# WalkieTalkie_Basic.net
KiCad netlist of a schematic drawn in EAGLE
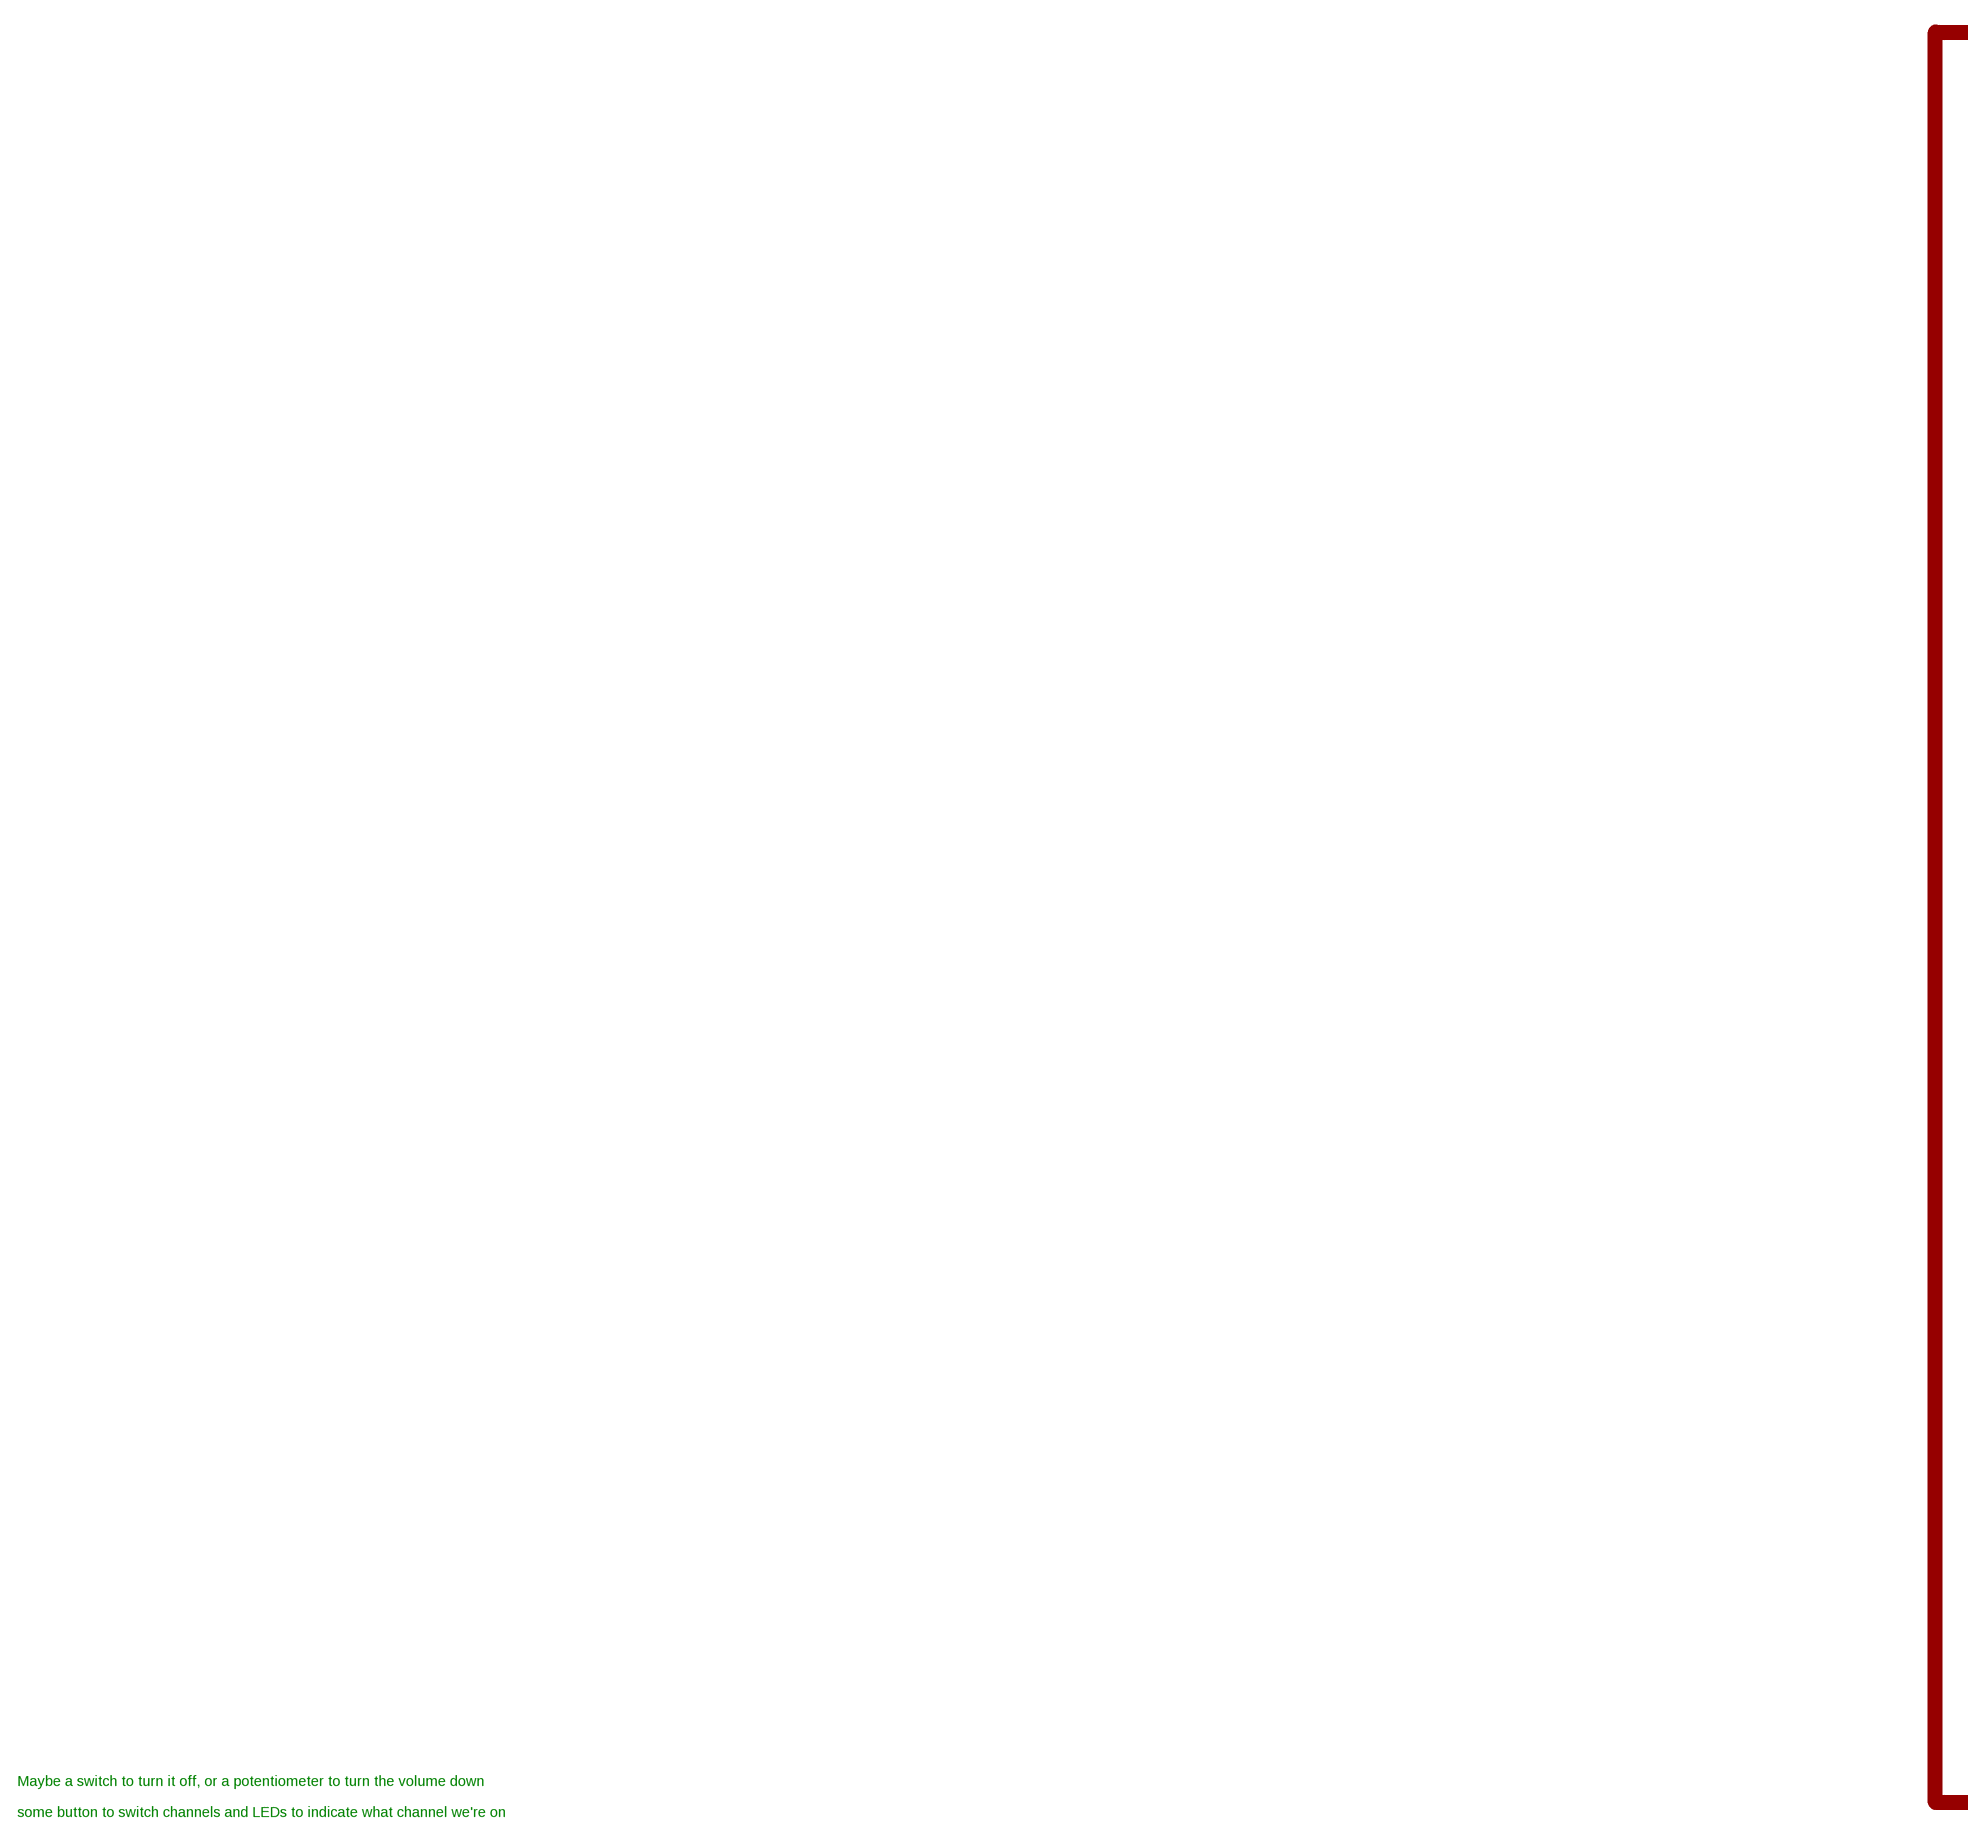
[diagram p0: schematic, sheet 1, part 1 of 2]
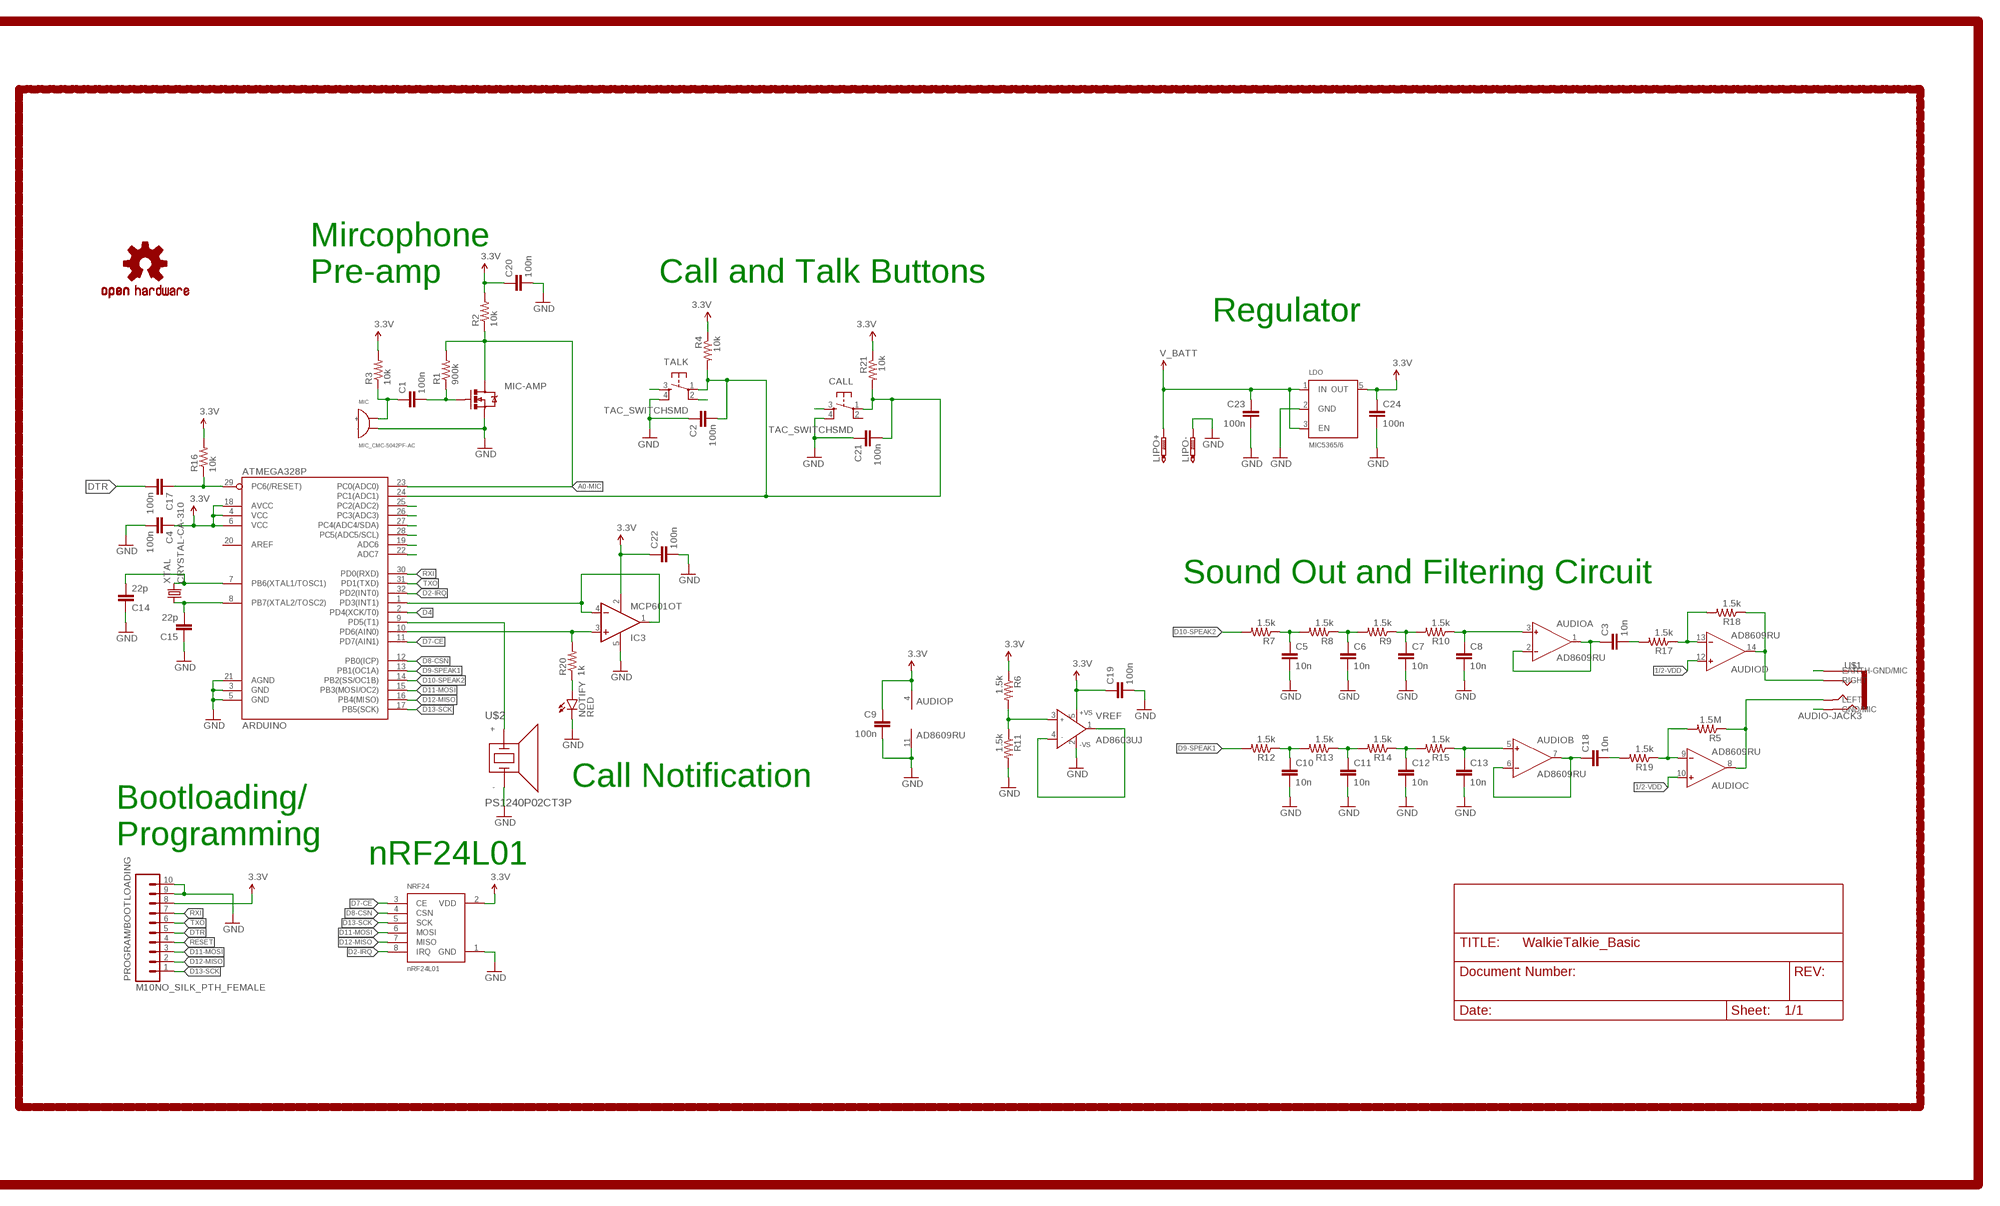
[diagram p1: schematic, sheet 1, part 2 of 2]

(export (version "E")
  (design (tool "Eeschema 10.0.6"))
  (components
    (comp (ref "ARDUINO")
      (value "ATMEGA328P")
      (footprint "eagle-import:TQFP32-08")
      (libsource (lib "eagle-import") (part "ATMEGA328_SMT-OHMOD"))
    )
    (comp (ref "AUDIO")
      (value "AD8609RU")
      (footprint "eagle-import:TSSOP14")
      (fields (field (name "MF") "ALTERA CORPORATION") (field (name "MPN") "AD8609ARUZ"))
      (libsource (lib "eagle-import") (part "AD8609RU"))
    )
    (comp (ref "C1")
      (value "100n")
      (footprint "eagle-import:C0402")
      (libsource (lib "eagle-import") (part "C-EUC0402"))
    )
    (comp (ref "C2")
      (value "100n")
      (footprint "eagle-import:C0402")
      (libsource (lib "eagle-import") (part "C-EUC0402"))
    )
    (comp (ref "C3")
      (value "10n")
      (footprint "eagle-import:C0402")
      (libsource (lib "eagle-import") (part "C-EUC0402"))
    )
    (comp (ref "C4")
      (value "100n")
      (footprint "eagle-import:C0402")
      (libsource (lib "eagle-import") (part "C-EUC0402"))
    )
    (comp (ref "C5")
      (value "10n")
      (footprint "eagle-import:C0402")
      (libsource (lib "eagle-import") (part "C-EUC0402"))
    )
    (comp (ref "C6")
      (value "10n")
      (footprint "eagle-import:C0402")
      (libsource (lib "eagle-import") (part "C-EUC0402"))
    )
    (comp (ref "C7")
      (value "10n")
      (footprint "eagle-import:C0402")
      (libsource (lib "eagle-import") (part "C-EUC0402"))
    )
    (comp (ref "C8")
      (value "10n")
      (footprint "eagle-import:C0402")
      (libsource (lib "eagle-import") (part "C-EUC0402"))
    )
    (comp (ref "C9")
      (value "100n")
      (footprint "eagle-import:C0402")
      (libsource (lib "eagle-import") (part "C-EUC0402"))
    )
    (comp (ref "C10")
      (value "10n")
      (footprint "eagle-import:C0402")
      (libsource (lib "eagle-import") (part "C-EUC0402"))
    )
    (comp (ref "C11")
      (value "10n")
      (footprint "eagle-import:C0402")
      (libsource (lib "eagle-import") (part "C-EUC0402"))
    )
    (comp (ref "C12")
      (value "10n")
      (footprint "eagle-import:C0402")
      (libsource (lib "eagle-import") (part "C-EUC0402"))
    )
    (comp (ref "C13")
      (value "10n")
      (footprint "eagle-import:C0402")
      (libsource (lib "eagle-import") (part "C-EUC0402"))
    )
    (comp (ref "C14")
      (value "22p")
      (footprint "eagle-import:C0402")
      (libsource (lib "eagle-import") (part "C-EUC0402"))
    )
    (comp (ref "C15")
      (value "22p")
      (footprint "eagle-import:C0402")
      (libsource (lib "eagle-import") (part "C-EUC0402"))
    )
    (comp (ref "C17")
      (value "100n")
      (footprint "eagle-import:C0402")
      (libsource (lib "eagle-import") (part "C-EUC0402"))
    )
    (comp (ref "C18")
      (value "10n")
      (footprint "eagle-import:C0402")
      (libsource (lib "eagle-import") (part "C-EUC0402"))
    )
    (comp (ref "C19")
      (value "100n")
      (footprint "eagle-import:C0402")
      (libsource (lib "eagle-import") (part "C-EUC0402"))
    )
    (comp (ref "C20")
      (value "100n")
      (footprint "eagle-import:C0402")
      (libsource (lib "eagle-import") (part "C-EUC0402"))
    )
    (comp (ref "C21")
      (value "100n")
      (footprint "eagle-import:C0402")
      (libsource (lib "eagle-import") (part "C-EUC0402"))
    )
    (comp (ref "C22")
      (value "100n")
      (footprint "eagle-import:C0402")
      (libsource (lib "eagle-import") (part "C-EUC0402"))
    )
    (comp (ref "C23")
      (value "100n")
      (footprint "eagle-import:C0402")
      (libsource (lib "eagle-import") (part "C-EUC0402"))
    )
    (comp (ref "C24")
      (value "100n")
      (footprint "eagle-import:C0402")
      (libsource (lib "eagle-import") (part "C-EUC0402"))
    )
    (comp (ref "CALL")
      (value "TAC_SWITCHSMD")
      (footprint "eagle-import:TACTILE-SWITCH-SMD")
      (libsource (lib "eagle-import") (part "TAC_SWITCHSMD"))
    )
    (comp (ref "IC3")
      (value "MCP601OT")
      (footprint "eagle-import:SOT23-5")
      (libsource (lib "eagle-import") (part "MCP601OT"))
    )
    (comp (ref "LDO")
      (value "MIC5365/6")
      (footprint "eagle-import:SC-70-5")
      (libsource (lib "eagle-import") (part "MIC5365/6"))
    )
    (comp (ref "LIPO")
      (value "BATT-CONNECT")
      (footprint "eagle-import:HOLE")
      (libsource (lib "eagle-import") (part "BATT-CONNECT"))
    )
    (comp (ref "LOGO1")
      (value "OSHW-LOGOS")
      (footprint "eagle-import:OSHW-LOGO-S")
      (libsource (lib "eagle-import") (part "OSHW-LOGOS"))
    )
    (comp (ref "MIC")
      (value "MIC_CMC-5042PF-AC")
      (footprint "eagle-import:MIC_01")
      (libsource (lib "eagle-import") (part "MIC_CMC-5042PF-AC"))
    )
    (comp (ref "MIC-AMP")
      (value "MOSFET-NCHANNELBSS123LT1G")
      (footprint "eagle-import:SOT23-3")
      (libsource (lib "eagle-import") (part "MOSFET-NCHANNELBSS123LT1G"))
    )
    (comp (ref "NOTIFY")
      (value "RED")
      (footprint "eagle-import:LED-0603")
      (libsource (lib "eagle-import") (part "LED-RED0603"))
    )
    (comp (ref "NRF24")
      (value "NRF24L01-BREAKOUT")
      (footprint "eagle-import:NRF24L01-BREAKOUT")
      (libsource (lib "eagle-import") (part "NRF24L01-BREAKOUT"))
    )
    (comp (ref "PROGRAM/BOOTLOADING")
      (value "M10NO_SILK_PTH_FEMALE")
      (footprint "eagle-import:1X10_NO_SILK")
      (libsource (lib "eagle-import") (part "M10NO_SILK_PTH_FEMALE"))
    )
    (comp (ref "R1")
      (value "900k")
      (footprint "eagle-import:R0402")
      (libsource (lib "eagle-import") (part "R-US_R0402"))
    )
    (comp (ref "R2")
      (value "10k")
      (footprint "eagle-import:R0402")
      (libsource (lib "eagle-import") (part "R-US_R0402"))
    )
    (comp (ref "R3")
      (value "10k")
      (footprint "eagle-import:R0402")
      (libsource (lib "eagle-import") (part "R-US_R0402"))
    )
    (comp (ref "R4")
      (value "10k")
      (footprint "eagle-import:R0402")
      (libsource (lib "eagle-import") (part "R-US_R0402"))
    )
    (comp (ref "R5")
      (value "1.5M")
      (footprint "eagle-import:R0402")
      (libsource (lib "eagle-import") (part "R-US_R0402"))
    )
    (comp (ref "R6")
      (value "1.5k")
      (footprint "eagle-import:R0402")
      (libsource (lib "eagle-import") (part "R-US_R0402"))
    )
    (comp (ref "R7")
      (value "1.5k")
      (footprint "eagle-import:R0402")
      (libsource (lib "eagle-import") (part "R-US_R0402"))
    )
    (comp (ref "R8")
      (value "1.5k")
      (footprint "eagle-import:R0402")
      (libsource (lib "eagle-import") (part "R-US_R0402"))
    )
    (comp (ref "R9")
      (value "1.5k")
      (footprint "eagle-import:R0402")
      (libsource (lib "eagle-import") (part "R-US_R0402"))
    )
    (comp (ref "R10")
      (value "1.5k")
      (footprint "eagle-import:R0402")
      (libsource (lib "eagle-import") (part "R-US_R0402"))
    )
    (comp (ref "R11")
      (value "1.5k")
      (footprint "eagle-import:R0402")
      (libsource (lib "eagle-import") (part "R-US_R0402"))
    )
    (comp (ref "R12")
      (value "1.5k")
      (footprint "eagle-import:R0402")
      (libsource (lib "eagle-import") (part "R-US_R0402"))
    )
    (comp (ref "R13")
      (value "1.5k")
      (footprint "eagle-import:R0402")
      (libsource (lib "eagle-import") (part "R-US_R0402"))
    )
    (comp (ref "R14")
      (value "1.5k")
      (footprint "eagle-import:R0402")
      (libsource (lib "eagle-import") (part "R-US_R0402"))
    )
    (comp (ref "R15")
      (value "1.5k")
      (footprint "eagle-import:R0402")
      (libsource (lib "eagle-import") (part "R-US_R0402"))
    )
    (comp (ref "R16")
      (value "10k")
      (footprint "eagle-import:R0402")
      (libsource (lib "eagle-import") (part "R-US_R0402"))
    )
    (comp (ref "R17")
      (value "1.5k")
      (footprint "eagle-import:R0402")
      (libsource (lib "eagle-import") (part "R-US_R0402"))
    )
    (comp (ref "R18")
      (value "1.5k")
      (footprint "eagle-import:R0402")
      (libsource (lib "eagle-import") (part "R-US_R0402"))
    )
    (comp (ref "R19")
      (value "1.5k")
      (footprint "eagle-import:R0402")
      (libsource (lib "eagle-import") (part "R-US_R0402"))
    )
    (comp (ref "R20")
      (value "1k")
      (footprint "eagle-import:R0402")
      (libsource (lib "eagle-import") (part "R-US_R0402"))
    )
    (comp (ref "R21")
      (value "10k")
      (footprint "eagle-import:R0402")
      (libsource (lib "eagle-import") (part "R-US_R0402"))
    )
    (comp (ref "TALK")
      (value "TAC_SWITCHSMD")
      (footprint "eagle-import:TACTILE-SWITCH-SMD")
      (libsource (lib "eagle-import") (part "TAC_SWITCHSMD"))
    )
    (comp (ref "U$1")
      (value "AUDIO-JACK3")
      (footprint "eagle-import:AUDIO-JACK-TRRS-SMD")
      (libsource (lib "eagle-import") (part "AUDIO-JACK3"))
    )
    (comp (ref "U$2")
      (value "PS1240P02CT3P")
      (footprint "eagle-import:PIEZO-1")
      (libsource (lib "eagle-import") (part "PS1240P02CT3P"))
    )
    (comp (ref "VREF")
      (value "AD8603UJ")
      (footprint "eagle-import:SOT23-5")
      (fields (field (name "MF") "ALTERA CORPORATION") (field (name "MPN") "AD8603AUJZ-REEL7"))
      (libsource (lib "eagle-import") (part "AD8603UJ"))
    )
    (comp (ref "XTAL")
      (value "CRYSTAL-CA-310")
      (footprint "eagle-import:CA-301")
      (libsource (lib "eagle-import") (part "CRYSTAL-CA-310"))
    )
  )
  (nets
    (net (code "1") (name "1{slash}2-VDD") (class "Default")
      (node (ref "AUDIO") (pin "10") (pinfunction "IN+_10") (pintype "input"))
      (node (ref "AUDIO") (pin "12") (pinfunction "IN+_12") (pintype "input"))
      (node (ref "VREF") (pin "1") (pinfunction "OUT_1") (pintype "output"))
      (node (ref "VREF") (pin "4") (pinfunction "IN-_4") (pintype "input"))
    )
    (net (code "2") (name "3.3V") (class "Default")
      (node (ref "ARDUINO") (pin "18") (pinfunction "AVCC_18") (pintype "bidirectional"))
      (node (ref "ARDUINO") (pin "4") (pinfunction "VCC_4") (pintype "bidirectional"))
      (node (ref "ARDUINO") (pin "6") (pinfunction "VCC_6") (pintype "bidirectional"))
      (node (ref "AUDIO") (pin "4") (pinfunction "V+_4") (pintype "power_in"))
      (node (ref "C19") (pin "1") (pinfunction "1_1") (pintype "passive"))
      (node (ref "C20") (pin "1") (pinfunction "1_1") (pintype "passive"))
      (node (ref "C22") (pin "1") (pinfunction "1_1") (pintype "passive"))
      (node (ref "C24") (pin "1") (pinfunction "1_1") (pintype "passive"))
      (node (ref "C4") (pin "1") (pinfunction "1_1") (pintype "passive"))
      (node (ref "C9") (pin "1") (pinfunction "1_1") (pintype "passive"))
      (node (ref "IC3") (pin "2") (pinfunction "V-_2") (pintype "power_in"))
      (node (ref "LDO") (pin "5") (pinfunction "OUT_5") (pintype "bidirectional"))
      (node (ref "NRF24") (pin "2") (pinfunction "VDD_2") (pintype "bidirectional"))
      (node (ref "PROGRAM/BOOTLOADING") (pin "8") (pinfunction "8_8") (pintype "passive"))
      (node (ref "R16") (pin "2") (pinfunction "2_2") (pintype "passive"))
      (node (ref "R2") (pin "2") (pinfunction "2_2") (pintype "passive"))
      (node (ref "R21") (pin "1") (pinfunction "1_1") (pintype "passive"))
      (node (ref "R3") (pin "2") (pinfunction "2_2") (pintype "passive"))
      (node (ref "R4") (pin "1") (pinfunction "1_1") (pintype "passive"))
      (node (ref "R6") (pin "1") (pinfunction "1_1") (pintype "passive"))
      (node (ref "VREF") (pin "5") (pinfunction "+VS_5") (pintype "input"))
    )
    (net (code "3") (name "A0-MIC") (class "Default")
      (node (ref "ARDUINO") (pin "23") (pinfunction "PC0(ADC0)_23") (pintype "bidirectional"))
      (node (ref "MIC-AMP") (pin "3") (pinfunction "D_3") (pintype "passive"))
      (node (ref "R1") (pin "2") (pinfunction "2_2") (pintype "passive"))
      (node (ref "R2") (pin "1") (pinfunction "1_1") (pintype "passive"))
    )
    (net (code "4") (name "D2-IRQ") (class "Default")
      (node (ref "ARDUINO") (pin "32") (pinfunction "PD2(INT0)_32") (pintype "bidirectional"))
      (node (ref "NRF24") (pin "8") (pinfunction "IRQ_8") (pintype "bidirectional"))
    )
    (net (code "5") (name "D4") (class "Default")
      (node (ref "ARDUINO") (pin "2") (pinfunction "PD4(XCK/T0)_2") (pintype "bidirectional"))
    )
    (net (code "6") (name "D7-CE") (class "Default")
      (node (ref "ARDUINO") (pin "11") (pinfunction "PD7(AIN1)_11") (pintype "bidirectional"))
      (node (ref "NRF24") (pin "3") (pinfunction "CE_3") (pintype "bidirectional"))
    )
    (net (code "7") (name "D8-CSN") (class "Default")
      (node (ref "ARDUINO") (pin "12") (pinfunction "PB0(ICP)_12") (pintype "bidirectional"))
      (node (ref "NRF24") (pin "4") (pinfunction "CSN_4") (pintype "bidirectional"))
    )
    (net (code "8") (name "D9-SPEAK1") (class "Default")
      (node (ref "ARDUINO") (pin "13") (pinfunction "PB1(OC1A)_13") (pintype "bidirectional"))
      (node (ref "R12") (pin "2") (pinfunction "2_2") (pintype "passive"))
    )
    (net (code "9") (name "D10-SPEAK2") (class "Default")
      (node (ref "ARDUINO") (pin "14") (pinfunction "PB2(SS/OC1B)_14") (pintype "bidirectional"))
      (node (ref "R7") (pin "2") (pinfunction "2_2") (pintype "passive"))
    )
    (net (code "10") (name "D11-MOSI") (class "Default")
      (node (ref "ARDUINO") (pin "15") (pinfunction "PB3(MOSI/OC2)_15") (pintype "bidirectional"))
      (node (ref "NRF24") (pin "6") (pinfunction "MOSI_6") (pintype "bidirectional"))
      (node (ref "PROGRAM/BOOTLOADING") (pin "3") (pinfunction "3_3") (pintype "passive"))
    )
    (net (code "11") (name "D12-MISO") (class "Default")
      (node (ref "ARDUINO") (pin "16") (pinfunction "PB4(MISO)_16") (pintype "bidirectional"))
      (node (ref "NRF24") (pin "7") (pinfunction "MISO_7") (pintype "bidirectional"))
      (node (ref "PROGRAM/BOOTLOADING") (pin "2") (pinfunction "2_2") (pintype "passive"))
    )
    (net (code "12") (name "D13-SCK") (class "Default")
      (node (ref "ARDUINO") (pin "17") (pinfunction "PB5(SCK)_17") (pintype "bidirectional"))
      (node (ref "NRF24") (pin "5") (pinfunction "SCK_5") (pintype "bidirectional"))
      (node (ref "PROGRAM/BOOTLOADING") (pin "1") (pinfunction "1_1") (pintype "passive"))
    )
    (net (code "13") (name "DTR") (class "Default")
      (node (ref "C17") (pin "2") (pinfunction "2_2") (pintype "passive"))
      (node (ref "PROGRAM/BOOTLOADING") (pin "5") (pinfunction "5_5") (pintype "passive"))
    )
    (net (code "14") (name "GND") (class "Default")
      (node (ref "ARDUINO") (pin "21") (pinfunction "AGND_21") (pintype "bidirectional"))
      (node (ref "ARDUINO") (pin "3") (pinfunction "GND_3") (pintype "bidirectional"))
      (node (ref "ARDUINO") (pin "5") (pinfunction "GND_5") (pintype "bidirectional"))
      (node (ref "AUDIO") (pin "11") (pinfunction "V-_11") (pintype "power_in"))
      (node (ref "C10") (pin "2") (pinfunction "2_2") (pintype "passive"))
      (node (ref "C11") (pin "2") (pinfunction "2_2") (pintype "passive"))
      (node (ref "C12") (pin "2") (pinfunction "2_2") (pintype "passive"))
      (node (ref "C13") (pin "2") (pinfunction "2_2") (pintype "passive"))
      (node (ref "C14") (pin "1") (pinfunction "1_1") (pintype "passive"))
      (node (ref "C15") (pin "1") (pinfunction "1_1") (pintype "passive"))
      (node (ref "C19") (pin "2") (pinfunction "2_2") (pintype "passive"))
      (node (ref "C2") (pin "1") (pinfunction "1_1") (pintype "passive"))
      (node (ref "C20") (pin "2") (pinfunction "2_2") (pintype "passive"))
      (node (ref "C21") (pin "1") (pinfunction "1_1") (pintype "passive"))
      (node (ref "C22") (pin "2") (pinfunction "2_2") (pintype "passive"))
      (node (ref "C23") (pin "2") (pinfunction "2_2") (pintype "passive"))
      (node (ref "C24") (pin "2") (pinfunction "2_2") (pintype "passive"))
      (node (ref "C4") (pin "2") (pinfunction "2_2") (pintype "passive"))
      (node (ref "C5") (pin "2") (pinfunction "2_2") (pintype "passive"))
      (node (ref "C6") (pin "2") (pinfunction "2_2") (pintype "passive"))
      (node (ref "C7") (pin "2") (pinfunction "2_2") (pintype "passive"))
      (node (ref "C8") (pin "2") (pinfunction "2_2") (pintype "passive"))
      (node (ref "C9") (pin "2") (pinfunction "2_2") (pintype "passive"))
      (node (ref "CALL") (pin "4") (pinfunction "4_4") (pintype "passive"))
      (node (ref "IC3") (pin "5") (pinfunction "V+_5") (pintype "power_in"))
      (node (ref "LDO") (pin "2") (pinfunction "GND_2") (pintype "bidirectional"))
      (node (ref "LIPO") (pin "P$2") (pinfunction "TP_P$2") (pintype "input"))
      (node (ref "MIC") (pin "-") (pinfunction "-_-") (pintype "bidirectional"))
      (node (ref "MIC-AMP") (pin "2") (pinfunction "S_2") (pintype "passive"))
      (node (ref "NOTIFY") (pin "C") (pinfunction "C_C") (pintype "passive"))
      (node (ref "NRF24") (pin "1") (pinfunction "GND_1") (pintype "bidirectional"))
      (node (ref "PROGRAM/BOOTLOADING") (pin "10") (pinfunction "10_10") (pintype "passive"))
      (node (ref "PROGRAM/BOOTLOADING") (pin "9") (pinfunction "9_9") (pintype "passive"))
      (node (ref "R11") (pin "2") (pinfunction "2_2") (pintype "passive"))
      (node (ref "TALK") (pin "4") (pinfunction "4_4") (pintype "passive"))
      (node (ref "U$2") (pin "-") (pinfunction "-_-") (pintype "bidirectional"))
      (node (ref "VREF") (pin "2") (pinfunction "-VS_2") (pintype "input"))
    )
    (net (code "15") (name "Net-(ARDUINO-PB6(XTAL1{slash}TOSC1))") (class "Default")
      (node (ref "ARDUINO") (pin "7") (pinfunction "PB6(XTAL1/TOSC1)_7") (pintype "bidirectional"))
      (node (ref "C14") (pin "2") (pinfunction "2_2") (pintype "passive"))
      (node (ref "XTAL") (pin "2") (pinfunction "2_2") (pintype "passive"))
    )
    (net (code "16") (name "Net-(ARDUINO-PB7(XTAL2{slash}TOSC2))") (class "Default")
      (node (ref "ARDUINO") (pin "8") (pinfunction "PB7(XTAL2/TOSC2)_8") (pintype "bidirectional"))
      (node (ref "C15") (pin "2") (pinfunction "2_2") (pintype "passive"))
      (node (ref "XTAL") (pin "1") (pinfunction "1_1") (pintype "passive"))
    )
    (net (code "17") (name "Net-(ARDUINO-PC1(ADC1))") (class "Default")
      (node (ref "ARDUINO") (pin "24") (pinfunction "PC1(ADC1)_24") (pintype "bidirectional"))
      (node (ref "C2") (pin "2") (pinfunction "2_2") (pintype "passive"))
      (node (ref "C21") (pin "2") (pinfunction "2_2") (pintype "passive"))
      (node (ref "CALL") (pin "1") (pinfunction "1_1") (pintype "passive"))
      (node (ref "R21") (pin "2") (pinfunction "2_2") (pintype "passive"))
      (node (ref "R4") (pin "2") (pinfunction "2_2") (pintype "passive"))
      (node (ref "TALK") (pin "1") (pinfunction "1_1") (pintype "passive"))
    )
    (net (code "18") (name "Net-(ARDUINO-PD3(INT1))") (class "Default")
      (node (ref "ARDUINO") (pin "1") (pinfunction "PD3(INT1)_1") (pintype "bidirectional"))
      (node (ref "IC3") (pin "1") (pinfunction "OUT_1") (pintype "output"))
      (node (ref "IC3") (pin "4") (pinfunction "-IN_4") (pintype "input"))
    )
    (net (code "19") (name "Net-(ARDUINO-PD5(T1))") (class "Default")
      (node (ref "ARDUINO") (pin "9") (pinfunction "PD5(T1)_9") (pintype "bidirectional"))
      (node (ref "U$2") (pin "+") (pinfunction "+_+") (pintype "bidirectional"))
    )
    (net (code "20") (name "Net-(ARDUINO-PD6(AIN0))") (class "Default")
      (node (ref "ARDUINO") (pin "10") (pinfunction "PD6(AIN0)_10") (pintype "bidirectional"))
      (node (ref "IC3") (pin "3") (pinfunction "+IN_3") (pintype "input"))
      (node (ref "R20") (pin "2") (pinfunction "2_2") (pintype "passive"))
    )
    (net (code "21") (name "Net-(AUDIOA-IN+)") (class "Default")
      (node (ref "AUDIO") (pin "3") (pinfunction "IN+_3") (pintype "input"))
      (node (ref "C8") (pin "1") (pinfunction "1_1") (pintype "passive"))
      (node (ref "R10") (pin "1") (pinfunction "1_1") (pintype "passive"))
    )
    (net (code "22") (name "Net-(AUDIOA-IN-)") (class "Default")
      (node (ref "AUDIO") (pin "1") (pinfunction "OUT_1") (pintype "output"))
      (node (ref "AUDIO") (pin "2") (pinfunction "IN-_2") (pintype "input"))
      (node (ref "C3") (pin "1") (pinfunction "1_1") (pintype "passive"))
    )
    (net (code "23") (name "Net-(AUDIOB-IN+)") (class "Default")
      (node (ref "AUDIO") (pin "5") (pinfunction "IN+_5") (pintype "input"))
      (node (ref "C13") (pin "1") (pinfunction "1_1") (pintype "passive"))
      (node (ref "R15") (pin "1") (pinfunction "1_1") (pintype "passive"))
    )
    (net (code "24") (name "Net-(AUDIOB-IN-)") (class "Default")
      (node (ref "AUDIO") (pin "6") (pinfunction "IN-_6") (pintype "input"))
      (node (ref "AUDIO") (pin "7") (pinfunction "OUT_7") (pintype "output"))
      (node (ref "C18") (pin "1") (pinfunction "1_1") (pintype "passive"))
    )
    (net (code "25") (name "Net-(AUDIOC-IN-)") (class "Default")
      (node (ref "AUDIO") (pin "9") (pinfunction "IN-_9") (pintype "input"))
      (node (ref "R19") (pin "1") (pinfunction "1_1") (pintype "passive"))
      (node (ref "R5") (pin "2") (pinfunction "2_2") (pintype "passive"))
    )
    (net (code "26") (name "Net-(AUDIOC-OUT)") (class "Default")
      (node (ref "AUDIO") (pin "8") (pinfunction "OUT_8") (pintype "output"))
      (node (ref "R5") (pin "1") (pinfunction "1_1") (pintype "passive"))
      (node (ref "U$1") (pin "TIP") (pinfunction "LEFT_TIP") (pintype "bidirectional"))
    )
    (net (code "27") (name "Net-(AUDIOD-IN-)") (class "Default")
      (node (ref "AUDIO") (pin "13") (pinfunction "IN-_13") (pintype "input"))
      (node (ref "R17") (pin "1") (pinfunction "1_1") (pintype "passive"))
      (node (ref "R18") (pin "2") (pinfunction "2_2") (pintype "passive"))
    )
    (net (code "28") (name "Net-(AUDIOD-OUT)") (class "Default")
      (node (ref "AUDIO") (pin "14") (pinfunction "OUT_14") (pintype "output"))
      (node (ref "R18") (pin "1") (pinfunction "1_1") (pintype "passive"))
      (node (ref "U$1") (pin "RING1") (pinfunction "RIGHT_RING1") (pintype "bidirectional"))
    )
    (net (code "29") (name "Net-(C1-Pad1)") (class "Default")
      (node (ref "C1") (pin "1") (pinfunction "1_1") (pintype "passive"))
      (node (ref "MIC") (pin "+") (pinfunction "+_+") (pintype "bidirectional"))
      (node (ref "R3") (pin "1") (pinfunction "1_1") (pintype "passive"))
    )
    (net (code "30") (name "Net-(C3-Pad2)") (class "Default")
      (node (ref "C3") (pin "2") (pinfunction "2_2") (pintype "passive"))
      (node (ref "R17") (pin "2") (pinfunction "2_2") (pintype "passive"))
    )
    (net (code "31") (name "Net-(C5-Pad1)") (class "Default")
      (node (ref "C5") (pin "1") (pinfunction "1_1") (pintype "passive"))
      (node (ref "R7") (pin "1") (pinfunction "1_1") (pintype "passive"))
      (node (ref "R8") (pin "2") (pinfunction "2_2") (pintype "passive"))
    )
    (net (code "32") (name "Net-(C6-Pad1)") (class "Default")
      (node (ref "C6") (pin "1") (pinfunction "1_1") (pintype "passive"))
      (node (ref "R8") (pin "1") (pinfunction "1_1") (pintype "passive"))
      (node (ref "R9") (pin "2") (pinfunction "2_2") (pintype "passive"))
    )
    (net (code "33") (name "Net-(C7-Pad1)") (class "Default")
      (node (ref "C7") (pin "1") (pinfunction "1_1") (pintype "passive"))
      (node (ref "R10") (pin "2") (pinfunction "2_2") (pintype "passive"))
      (node (ref "R9") (pin "1") (pinfunction "1_1") (pintype "passive"))
    )
    (net (code "34") (name "Net-(C10-Pad1)") (class "Default")
      (node (ref "C10") (pin "1") (pinfunction "1_1") (pintype "passive"))
      (node (ref "R12") (pin "1") (pinfunction "1_1") (pintype "passive"))
      (node (ref "R13") (pin "2") (pinfunction "2_2") (pintype "passive"))
    )
    (net (code "35") (name "Net-(C11-Pad1)") (class "Default")
      (node (ref "C11") (pin "1") (pinfunction "1_1") (pintype "passive"))
      (node (ref "R13") (pin "1") (pinfunction "1_1") (pintype "passive"))
      (node (ref "R14") (pin "2") (pinfunction "2_2") (pintype "passive"))
    )
    (net (code "36") (name "Net-(C12-Pad1)") (class "Default")
      (node (ref "C12") (pin "1") (pinfunction "1_1") (pintype "passive"))
      (node (ref "R14") (pin "1") (pinfunction "1_1") (pintype "passive"))
      (node (ref "R15") (pin "2") (pinfunction "2_2") (pintype "passive"))
    )
    (net (code "37") (name "Net-(C18-Pad2)") (class "Default")
      (node (ref "C18") (pin "2") (pinfunction "2_2") (pintype "passive"))
      (node (ref "R19") (pin "2") (pinfunction "2_2") (pintype "passive"))
    )
    (net (code "38") (name "Net-(MIC-AMP-G)") (class "Default")
      (node (ref "C1") (pin "2") (pinfunction "2_2") (pintype "passive"))
      (node (ref "MIC-AMP") (pin "1") (pinfunction "G_1") (pintype "passive"))
      (node (ref "R1") (pin "1") (pinfunction "1_1") (pintype "passive"))
    )
    (net (code "39") (name "Net-(NOTIFY-PadA)") (class "Default")
      (node (ref "NOTIFY") (pin "A") (pinfunction "A_A") (pintype "passive"))
      (node (ref "R20") (pin "1") (pinfunction "1_1") (pintype "passive"))
    )
    (net (code "40") (name "Net-(VREF-IN+)") (class "Default")
      (node (ref "R11") (pin "1") (pinfunction "1_1") (pintype "passive"))
      (node (ref "R6") (pin "2") (pinfunction "2_2") (pintype "passive"))
      (node (ref "VREF") (pin "3") (pinfunction "IN+_3") (pintype "input"))
    )
    (net (code "41") (name "RESET") (class "Default")
      (node (ref "ARDUINO") (pin "29") (pinfunction "PC6(/RESET)_29") (pintype "bidirectional"))
      (node (ref "C17") (pin "1") (pinfunction "1_1") (pintype "passive"))
      (node (ref "PROGRAM/BOOTLOADING") (pin "4") (pinfunction "4_4") (pintype "passive"))
      (node (ref "R16") (pin "1") (pinfunction "1_1") (pintype "passive"))
    )
    (net (code "42") (name "RXI") (class "Default")
      (node (ref "ARDUINO") (pin "30") (pinfunction "PD0(RXD)_30") (pintype "bidirectional"))
      (node (ref "PROGRAM/BOOTLOADING") (pin "7") (pinfunction "7_7") (pintype "passive"))
    )
    (net (code "43") (name "TXO") (class "Default")
      (node (ref "ARDUINO") (pin "31") (pinfunction "PD1(TXD)_31") (pintype "bidirectional"))
      (node (ref "PROGRAM/BOOTLOADING") (pin "6") (pinfunction "6_6") (pintype "passive"))
    )
    (net (code "44") (name "V_BATT") (class "Default")
      (node (ref "C23") (pin "1") (pinfunction "1_1") (pintype "passive"))
      (node (ref "LDO") (pin "1") (pinfunction "IN_1") (pintype "bidirectional"))
      (node (ref "LDO") (pin "3") (pinfunction "EN_3") (pintype "bidirectional"))
      (node (ref "LIPO") (pin "P$1") (pinfunction "TP_P$1") (pintype "input"))
    )
    (net (code "45") (name "unconnected-(ARDUINO-ADC6-Pad19)") (class "Default")
      (node (ref "ARDUINO") (pin "19") (pinfunction "ADC6_19") (pintype "bidirectional"))
    )
    (net (code "46") (name "unconnected-(ARDUINO-ADC7-Pad22)") (class "Default")
      (node (ref "ARDUINO") (pin "22") (pinfunction "ADC7_22") (pintype "bidirectional"))
    )
    (net (code "47") (name "unconnected-(ARDUINO-AREF-Pad20)") (class "Default")
      (node (ref "ARDUINO") (pin "20") (pinfunction "AREF_20") (pintype "bidirectional"))
    )
    (net (code "48") (name "unconnected-(ARDUINO-PC2(ADC2)-Pad25)") (class "Default")
      (node (ref "ARDUINO") (pin "25") (pinfunction "PC2(ADC2)_25") (pintype "bidirectional"))
    )
    (net (code "49") (name "unconnected-(ARDUINO-PC3(ADC3)-Pad26)") (class "Default")
      (node (ref "ARDUINO") (pin "26") (pinfunction "PC3(ADC3)_26") (pintype "bidirectional"))
    )
    (net (code "50") (name "unconnected-(ARDUINO-PC4(ADC4{slash}SDA)-Pad27)") (class "Default")
      (node (ref "ARDUINO") (pin "27") (pinfunction "PC4(ADC4/SDA)_27") (pintype "bidirectional"))
    )
    (net (code "51") (name "unconnected-(ARDUINO-PC5(ADC5{slash}SCL)-Pad28)") (class "Default")
      (node (ref "ARDUINO") (pin "28") (pinfunction "PC5(ADC5/SCL)_28") (pintype "bidirectional"))
    )
    (net (code "52") (name "unconnected-(CALL-Pad2)") (class "Default")
      (node (ref "CALL") (pin "2") (pinfunction "2_2") (pintype "passive"))
    )
    (net (code "53") (name "unconnected-(CALL-Pad3)") (class "Default")
      (node (ref "CALL") (pin "3") (pinfunction "3_3") (pintype "passive"))
    )
    (net (code "54") (name "unconnected-(TALK-Pad2)") (class "Default")
      (node (ref "TALK") (pin "2") (pinfunction "2_2") (pintype "passive"))
    )
    (net (code "55") (name "unconnected-(TALK-Pad3)") (class "Default")
      (node (ref "TALK") (pin "3") (pinfunction "3_3") (pintype "passive"))
    )
    (net (code "56") (name "unconnected-(U$1-EARTH-GND{slash}MIC-PadEARTH)") (class "Default")
      (node (ref "U$1") (pin "EARTH") (pinfunction "EARTH-GND/MIC_EARTH") (pintype "bidirectional"))
    )
    (net (code "57") (name "unconnected-(U$1-GND{slash}MIC-PadRING2)") (class "Default")
      (node (ref "U$1") (pin "RING2") (pinfunction "GND/MIC_RING2") (pintype "bidirectional"))
    )
  )
)
